# AteGates.net
KiCad netlist of a schematic drawn in EAGLE
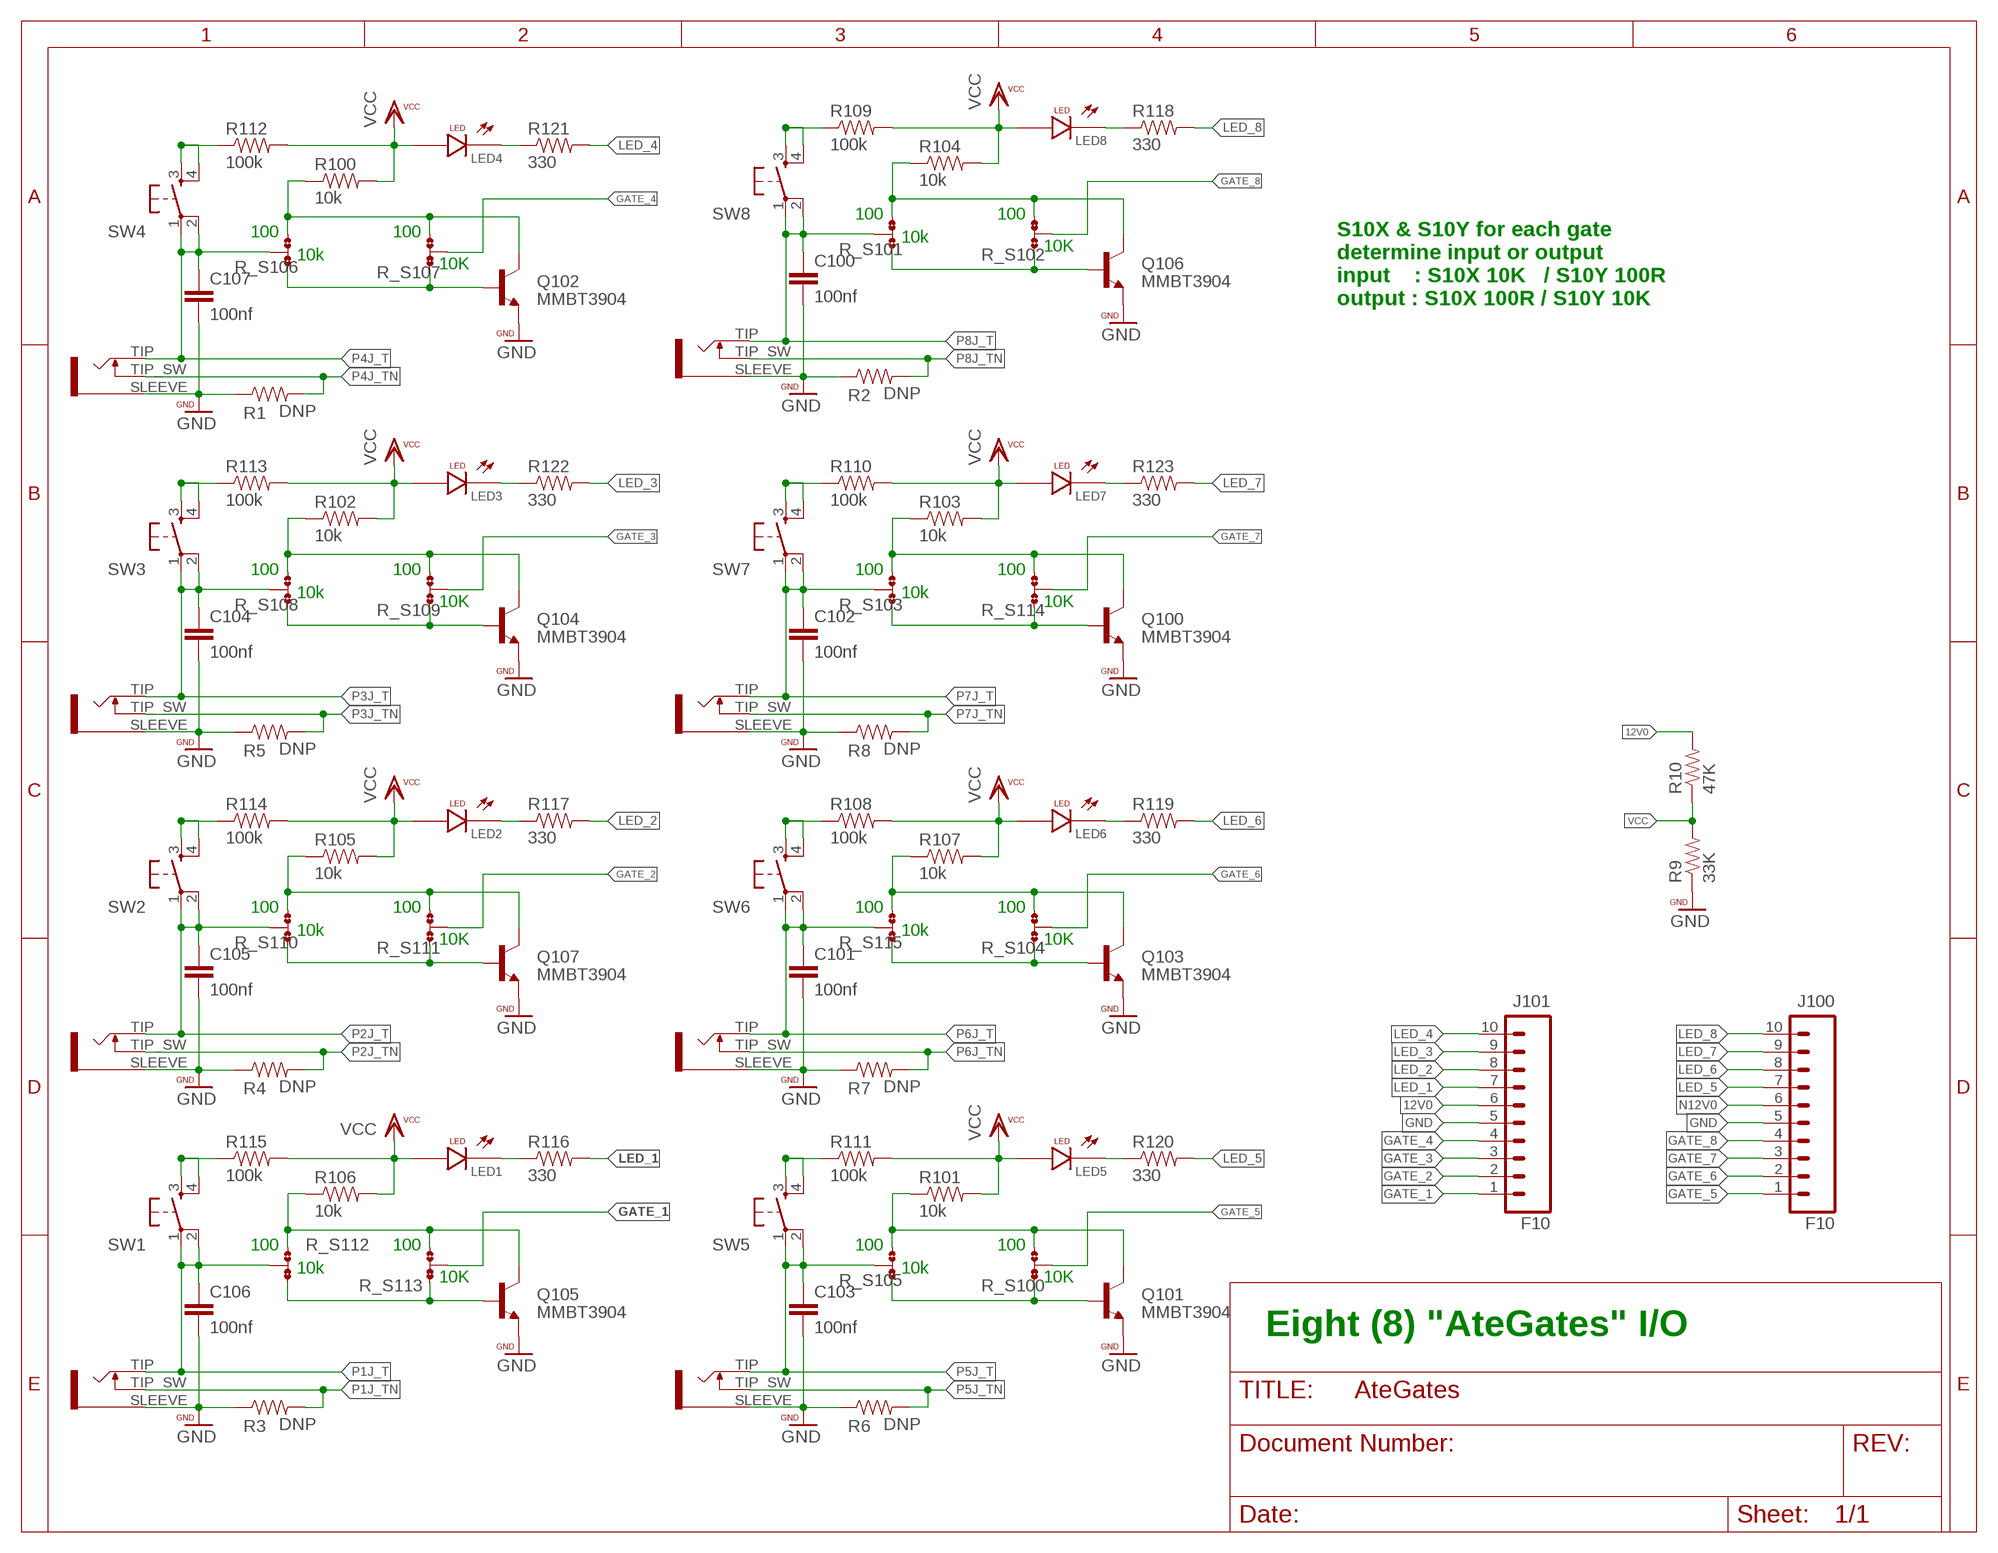
[diagram p0: schematic, sheet 1]

(export (version "E")
  (design (tool "Eeschema 10.0.6"))
  (components
    (comp (ref "C100")
      (value "100nf")
      (footprint "eagle-import:0603-CAP")
      (libsource (lib "eagle-import") (part "CAP0603-CAP"))
    )
    (comp (ref "C101")
      (value "100nf")
      (footprint "eagle-import:0603-CAP")
      (libsource (lib "eagle-import") (part "CAP0603-CAP"))
    )
    (comp (ref "C102")
      (value "100nf")
      (footprint "eagle-import:0603-CAP")
      (libsource (lib "eagle-import") (part "CAP0603-CAP"))
    )
    (comp (ref "C103")
      (value "100nf")
      (footprint "eagle-import:0603-CAP")
      (libsource (lib "eagle-import") (part "CAP0603-CAP"))
    )
    (comp (ref "C104")
      (value "100nf")
      (footprint "eagle-import:0603-CAP")
      (libsource (lib "eagle-import") (part "CAP0603-CAP"))
    )
    (comp (ref "C105")
      (value "100nf")
      (footprint "eagle-import:0603-CAP")
      (libsource (lib "eagle-import") (part "CAP0603-CAP"))
    )
    (comp (ref "C106")
      (value "100nf")
      (footprint "eagle-import:0603-CAP")
      (libsource (lib "eagle-import") (part "CAP0603-CAP"))
    )
    (comp (ref "C107")
      (value "100nf")
      (footprint "eagle-import:0603-CAP")
      (libsource (lib "eagle-import") (part "CAP0603-CAP"))
    )
    (comp (ref "J100")
      (value "F10")
      (footprint "eagle-import:1X10_OCTO")
      (libsource (lib "eagle-import") (part "M10SILK_FEMALE_PTH"))
    )
    (comp (ref "J101")
      (value "F10")
      (footprint "eagle-import:1X10_OCTO")
      (libsource (lib "eagle-import") (part "M10SILK_FEMALE_PTH"))
    )
    (comp (ref "LED1")
      (value "LED")
      (footprint "eagle-import:LED3MM")
      (libsource (lib "eagle-import") (part "LED"))
    )
    (comp (ref "LED2")
      (value "LED")
      (footprint "eagle-import:LED3MM")
      (libsource (lib "eagle-import") (part "LED"))
    )
    (comp (ref "LED3")
      (value "LED")
      (footprint "eagle-import:LED3MM")
      (libsource (lib "eagle-import") (part "LED"))
    )
    (comp (ref "LED4")
      (value "LED")
      (footprint "eagle-import:LED3MM")
      (libsource (lib "eagle-import") (part "LED"))
    )
    (comp (ref "LED5")
      (value "LED")
      (footprint "eagle-import:LED3MM")
      (libsource (lib "eagle-import") (part "LED"))
    )
    (comp (ref "LED6")
      (value "LED")
      (footprint "eagle-import:LED3MM")
      (libsource (lib "eagle-import") (part "LED"))
    )
    (comp (ref "LED7")
      (value "LED")
      (footprint "eagle-import:LED3MM")
      (libsource (lib "eagle-import") (part "LED"))
    )
    (comp (ref "LED8")
      (value "LED")
      (footprint "eagle-import:LED3MM")
      (libsource (lib "eagle-import") (part "LED"))
    )
    (comp (ref "P1J")
      (value "JACK-3_5MM-MONO-SW-WQP_PJ302-12")
      (footprint "eagle-import:WQP_PJ301M-12")
      (libsource (lib "eagle-import") (part "JACK-3_5MM-MONO-SW-WQP_PJ302-12"))
    )
    (comp (ref "P2J")
      (value "JACK-3_5MM-MONO-SW-WQP_PJ302-12")
      (footprint "eagle-import:WQP_PJ301M-12")
      (libsource (lib "eagle-import") (part "JACK-3_5MM-MONO-SW-WQP_PJ302-12"))
    )
    (comp (ref "P3J")
      (value "JACK-3_5MM-MONO-SW-WQP_PJ302-12")
      (footprint "eagle-import:WQP_PJ301M-12")
      (libsource (lib "eagle-import") (part "JACK-3_5MM-MONO-SW-WQP_PJ302-12"))
    )
    (comp (ref "P4J")
      (value "JACK-3_5MM-MONO-SW-WQP_PJ302-12")
      (footprint "eagle-import:WQP_PJ301M-12")
      (libsource (lib "eagle-import") (part "JACK-3_5MM-MONO-SW-WQP_PJ302-12"))
    )
    (comp (ref "P5J")
      (value "JACK-3_5MM-MONO-SW-WQP_PJ302-12")
      (footprint "eagle-import:WQP_PJ301M-12")
      (libsource (lib "eagle-import") (part "JACK-3_5MM-MONO-SW-WQP_PJ302-12"))
    )
    (comp (ref "P6J")
      (value "JACK-3_5MM-MONO-SW-WQP_PJ302-12")
      (footprint "eagle-import:WQP_PJ301M-12")
      (libsource (lib "eagle-import") (part "JACK-3_5MM-MONO-SW-WQP_PJ302-12"))
    )
    (comp (ref "P7J")
      (value "JACK-3_5MM-MONO-SW-WQP_PJ302-12")
      (footprint "eagle-import:WQP_PJ301M-12")
      (libsource (lib "eagle-import") (part "JACK-3_5MM-MONO-SW-WQP_PJ302-12"))
    )
    (comp (ref "P8J")
      (value "JACK-3_5MM-MONO-SW-WQP_PJ302-12")
      (footprint "eagle-import:WQP_PJ301M-12")
      (libsource (lib "eagle-import") (part "JACK-3_5MM-MONO-SW-WQP_PJ302-12"))
    )
    (comp (ref "Q100")
      (value "MMBT3904")
      (footprint "eagle-import:SOT23-BEC")
      (libsource (lib "eagle-import") (part "-NPN-SOT23-BECMMBT3904LT1"))
    )
    (comp (ref "Q101")
      (value "MMBT3904")
      (footprint "eagle-import:SOT23-BEC")
      (libsource (lib "eagle-import") (part "-NPN-SOT23-BECMMBT3904LT1"))
    )
    (comp (ref "Q102")
      (value "MMBT3904")
      (footprint "eagle-import:SOT23-BEC")
      (libsource (lib "eagle-import") (part "-NPN-SOT23-BECMMBT3904LT1"))
    )
    (comp (ref "Q103")
      (value "MMBT3904")
      (footprint "eagle-import:SOT23-BEC")
      (libsource (lib "eagle-import") (part "-NPN-SOT23-BECMMBT3904LT1"))
    )
    (comp (ref "Q104")
      (value "MMBT3904")
      (footprint "eagle-import:SOT23-BEC")
      (libsource (lib "eagle-import") (part "-NPN-SOT23-BECMMBT3904LT1"))
    )
    (comp (ref "Q105")
      (value "MMBT3904")
      (footprint "eagle-import:SOT23-BEC")
      (libsource (lib "eagle-import") (part "-NPN-SOT23-BECMMBT3904LT1"))
    )
    (comp (ref "Q106")
      (value "MMBT3904")
      (footprint "eagle-import:SOT23-BEC")
      (libsource (lib "eagle-import") (part "-NPN-SOT23-BECMMBT3904LT1"))
    )
    (comp (ref "Q107")
      (value "MMBT3904")
      (footprint "eagle-import:SOT23-BEC")
      (libsource (lib "eagle-import") (part "-NPN-SOT23-BECMMBT3904LT1"))
    )
    (comp (ref "R1")
      (value "DNP")
      (footprint "eagle-import:0603-RES")
      (libsource (lib "eagle-import") (part "RESISTOR0603-RES"))
    )
    (comp (ref "R2")
      (value "DNP")
      (footprint "eagle-import:0603-RES")
      (libsource (lib "eagle-import") (part "RESISTOR0603-RES"))
    )
    (comp (ref "R3")
      (value "DNP")
      (footprint "eagle-import:0603-RES")
      (libsource (lib "eagle-import") (part "RESISTOR0603-RES"))
    )
    (comp (ref "R4")
      (value "DNP")
      (footprint "eagle-import:0603-RES")
      (libsource (lib "eagle-import") (part "RESISTOR0603-RES"))
    )
    (comp (ref "R5")
      (value "DNP")
      (footprint "eagle-import:0603-RES")
      (libsource (lib "eagle-import") (part "RESISTOR0603-RES"))
    )
    (comp (ref "R6")
      (value "DNP")
      (footprint "eagle-import:0603-RES")
      (libsource (lib "eagle-import") (part "RESISTOR0603-RES"))
    )
    (comp (ref "R7")
      (value "DNP")
      (footprint "eagle-import:0603-RES")
      (libsource (lib "eagle-import") (part "RESISTOR0603-RES"))
    )
    (comp (ref "R8")
      (value "DNP")
      (footprint "eagle-import:0603-RES")
      (libsource (lib "eagle-import") (part "RESISTOR0603-RES"))
    )
    (comp (ref "R9")
      (value "33K")
      (footprint "eagle-import:0603-RES")
      (libsource (lib "eagle-import") (part "RESISTOR0603-RES"))
    )
    (comp (ref "R10")
      (value "47K")
      (footprint "eagle-import:0603-RES")
      (libsource (lib "eagle-import") (part "RESISTOR0603-RES"))
    )
    (comp (ref "R100")
      (value "10k")
      (footprint "eagle-import:0603-RES")
      (libsource (lib "eagle-import") (part "RESISTOR0603-RES"))
    )
    (comp (ref "R101")
      (value "10k")
      (footprint "eagle-import:0603-RES")
      (libsource (lib "eagle-import") (part "RESISTOR0603-RES"))
    )
    (comp (ref "R102")
      (value "10k")
      (footprint "eagle-import:0603-RES")
      (libsource (lib "eagle-import") (part "RESISTOR0603-RES"))
    )
    (comp (ref "R103")
      (value "10k")
      (footprint "eagle-import:0603-RES")
      (libsource (lib "eagle-import") (part "RESISTOR0603-RES"))
    )
    (comp (ref "R104")
      (value "10k")
      (footprint "eagle-import:0603-RES")
      (libsource (lib "eagle-import") (part "RESISTOR0603-RES"))
    )
    (comp (ref "R105")
      (value "10k")
      (footprint "eagle-import:0603-RES")
      (libsource (lib "eagle-import") (part "RESISTOR0603-RES"))
    )
    (comp (ref "R106")
      (value "10k")
      (footprint "eagle-import:0603-RES")
      (libsource (lib "eagle-import") (part "RESISTOR0603-RES"))
    )
    (comp (ref "R107")
      (value "10k")
      (footprint "eagle-import:0603-RES")
      (libsource (lib "eagle-import") (part "RESISTOR0603-RES"))
    )
    (comp (ref "R108")
      (value "100k")
      (footprint "eagle-import:0603-RES")
      (libsource (lib "eagle-import") (part "RESISTOR0603-RES"))
    )
    (comp (ref "R109")
      (value "100k")
      (footprint "eagle-import:0603-RES")
      (libsource (lib "eagle-import") (part "RESISTOR0603-RES"))
    )
    (comp (ref "R110")
      (value "100k")
      (footprint "eagle-import:0603-RES")
      (libsource (lib "eagle-import") (part "RESISTOR0603-RES"))
    )
    (comp (ref "R111")
      (value "100k")
      (footprint "eagle-import:0603-RES")
      (libsource (lib "eagle-import") (part "RESISTOR0603-RES"))
    )
    (comp (ref "R112")
      (value "100k")
      (footprint "eagle-import:0603-RES")
      (libsource (lib "eagle-import") (part "RESISTOR0603-RES"))
    )
    (comp (ref "R113")
      (value "100k")
      (footprint "eagle-import:0603-RES")
      (libsource (lib "eagle-import") (part "RESISTOR0603-RES"))
    )
    (comp (ref "R114")
      (value "100k")
      (footprint "eagle-import:0603-RES")
      (libsource (lib "eagle-import") (part "RESISTOR0603-RES"))
    )
    (comp (ref "R115")
      (value "100k")
      (footprint "eagle-import:0603-RES")
      (libsource (lib "eagle-import") (part "RESISTOR0603-RES"))
    )
    (comp (ref "R116")
      (value "330")
      (footprint "eagle-import:0603-RES")
      (libsource (lib "eagle-import") (part "RESISTOR0603-RES"))
    )
    (comp (ref "R117")
      (value "330")
      (footprint "eagle-import:0603-RES")
      (libsource (lib "eagle-import") (part "RESISTOR0603-RES"))
    )
    (comp (ref "R118")
      (value "330")
      (footprint "eagle-import:0603-RES")
      (libsource (lib "eagle-import") (part "RESISTOR0603-RES"))
    )
    (comp (ref "R119")
      (value "330")
      (footprint "eagle-import:0603-RES")
      (libsource (lib "eagle-import") (part "RESISTOR0603-RES"))
    )
    (comp (ref "R120")
      (value "330")
      (footprint "eagle-import:0603-RES")
      (libsource (lib "eagle-import") (part "RESISTOR0603-RES"))
    )
    (comp (ref "R121")
      (value "330")
      (footprint "eagle-import:0603-RES")
      (libsource (lib "eagle-import") (part "RESISTOR0603-RES"))
    )
    (comp (ref "R122")
      (value "330")
      (footprint "eagle-import:0603-RES")
      (libsource (lib "eagle-import") (part "RESISTOR0603-RES"))
    )
    (comp (ref "R123")
      (value "330")
      (footprint "eagle-import:0603-RES")
      (libsource (lib "eagle-import") (part "RESISTOR0603-RES"))
    )
    (comp (ref "R_S100")
      (value "JMP-3-NO-0603")
      (footprint "eagle-import:JMP-3-NO-0603")
      (libsource (lib "eagle-import") (part "JMP-3-NO-0603"))
    )
    (comp (ref "R_S101")
      (value "100")
      (footprint "eagle-import:JMP-3-NO-0603")
      (libsource (lib "eagle-import") (part "JMP-3-NO-0603"))
    )
    (comp (ref "R_S102")
      (value "JMP-3-NO-0603")
      (footprint "eagle-import:JMP-3-NO-0603")
      (libsource (lib "eagle-import") (part "JMP-3-NO-0603"))
    )
    (comp (ref "R_S103")
      (value "100")
      (footprint "eagle-import:JMP-3-NO-0603")
      (libsource (lib "eagle-import") (part "JMP-3-NO-0603"))
    )
    (comp (ref "R_S104")
      (value "JMP-3-NO-0603")
      (footprint "eagle-import:JMP-3-NO-0603")
      (libsource (lib "eagle-import") (part "JMP-3-NO-0603"))
    )
    (comp (ref "R_S105")
      (value "100")
      (footprint "eagle-import:JMP-3-NO-0603")
      (libsource (lib "eagle-import") (part "JMP-3-NO-0603"))
    )
    (comp (ref "R_S106")
      (value "100")
      (footprint "eagle-import:JMP-3-NO-0603")
      (libsource (lib "eagle-import") (part "JMP-3-NO-0603"))
    )
    (comp (ref "R_S107")
      (value "JMP-3-NO-0603")
      (footprint "eagle-import:JMP-3-NO-0603")
      (libsource (lib "eagle-import") (part "JMP-3-NO-0603"))
    )
    (comp (ref "R_S108")
      (value "100")
      (footprint "eagle-import:JMP-3-NO-0603")
      (libsource (lib "eagle-import") (part "JMP-3-NO-0603"))
    )
    (comp (ref "R_S109")
      (value "JMP-3-NO-0603")
      (footprint "eagle-import:JMP-3-NO-0603")
      (libsource (lib "eagle-import") (part "JMP-3-NO-0603"))
    )
    (comp (ref "R_S110")
      (value "100")
      (footprint "eagle-import:JMP-3-NO-0603")
      (libsource (lib "eagle-import") (part "JMP-3-NO-0603"))
    )
    (comp (ref "R_S111")
      (value "JMP-3-NO-0603")
      (footprint "eagle-import:JMP-3-NO-0603")
      (libsource (lib "eagle-import") (part "JMP-3-NO-0603"))
    )
    (comp (ref "R_S112")
      (value "100")
      (footprint "eagle-import:JMP-3-NO-0603")
      (libsource (lib "eagle-import") (part "JMP-3-NO-0603"))
    )
    (comp (ref "R_S113")
      (value "JMP-3-NO-0603")
      (footprint "eagle-import:JMP-3-NO-0603")
      (libsource (lib "eagle-import") (part "JMP-3-NO-0603"))
    )
    (comp (ref "R_S114")
      (value "JMP-3-NO-0603")
      (footprint "eagle-import:JMP-3-NO-0603")
      (libsource (lib "eagle-import") (part "JMP-3-NO-0603"))
    )
    (comp (ref "R_S115")
      (value "100")
      (footprint "eagle-import:JMP-3-NO-0603")
      (libsource (lib "eagle-import") (part "JMP-3-NO-0603"))
    )
    (comp (ref "SW1")
      (value "TAC_SWITCHPTH")
      (footprint "eagle-import:TACTILE-PTH")
      (libsource (lib "eagle-import") (part "TAC_SWITCHPTH"))
    )
    (comp (ref "SW2")
      (value "TAC_SWITCHPTH")
      (footprint "eagle-import:TACTILE-PTH")
      (libsource (lib "eagle-import") (part "TAC_SWITCHPTH"))
    )
    (comp (ref "SW3")
      (value "TAC_SWITCHPTH")
      (footprint "eagle-import:TACTILE-PTH")
      (libsource (lib "eagle-import") (part "TAC_SWITCHPTH"))
    )
    (comp (ref "SW4")
      (value "TAC_SWITCHPTH")
      (footprint "eagle-import:TACTILE-PTH")
      (libsource (lib "eagle-import") (part "TAC_SWITCHPTH"))
    )
    (comp (ref "SW5")
      (value "TAC_SWITCHPTH")
      (footprint "eagle-import:TACTILE-PTH")
      (libsource (lib "eagle-import") (part "TAC_SWITCHPTH"))
    )
    (comp (ref "SW6")
      (value "TAC_SWITCHPTH")
      (footprint "eagle-import:TACTILE-PTH")
      (libsource (lib "eagle-import") (part "TAC_SWITCHPTH"))
    )
    (comp (ref "SW7")
      (value "TAC_SWITCHPTH")
      (footprint "eagle-import:TACTILE-PTH")
      (libsource (lib "eagle-import") (part "TAC_SWITCHPTH"))
    )
    (comp (ref "SW8")
      (value "TAC_SWITCHPTH")
      (footprint "eagle-import:TACTILE-PTH")
      (libsource (lib "eagle-import") (part "TAC_SWITCHPTH"))
    )
  )
  (nets
    (net (code "1") (name "12V0") (class "Default")
      (node (ref "J101") (pin "6") (pinfunction "6_6") (pintype "passive"))
      (node (ref "R10") (pin "2") (pinfunction "2_2") (pintype "passive"))
    )
    (net (code "2") (name "GATE_1") (class "Default")
      (node (ref "J101") (pin "1") (pinfunction "1_1") (pintype "passive"))
      (node (ref "R_S113") (pin "2") (pinfunction "2_2") (pintype "passive"))
    )
    (net (code "3") (name "GATE_2") (class "Default")
      (node (ref "J101") (pin "2") (pinfunction "2_2") (pintype "passive"))
      (node (ref "R_S111") (pin "2") (pinfunction "2_2") (pintype "passive"))
    )
    (net (code "4") (name "GATE_3") (class "Default")
      (node (ref "J101") (pin "3") (pinfunction "3_3") (pintype "passive"))
      (node (ref "R_S109") (pin "2") (pinfunction "2_2") (pintype "passive"))
    )
    (net (code "5") (name "GATE_4") (class "Default")
      (node (ref "J101") (pin "4") (pinfunction "4_4") (pintype "passive"))
      (node (ref "R_S107") (pin "2") (pinfunction "2_2") (pintype "passive"))
    )
    (net (code "6") (name "GATE_5") (class "Default")
      (node (ref "J100") (pin "1") (pinfunction "1_1") (pintype "passive"))
      (node (ref "R_S100") (pin "2") (pinfunction "2_2") (pintype "passive"))
    )
    (net (code "7") (name "GATE_6") (class "Default")
      (node (ref "J100") (pin "2") (pinfunction "2_2") (pintype "passive"))
      (node (ref "R_S104") (pin "2") (pinfunction "2_2") (pintype "passive"))
    )
    (net (code "8") (name "GATE_7") (class "Default")
      (node (ref "J100") (pin "3") (pinfunction "3_3") (pintype "passive"))
      (node (ref "R_S114") (pin "2") (pinfunction "2_2") (pintype "passive"))
    )
    (net (code "9") (name "GATE_8") (class "Default")
      (node (ref "J100") (pin "4") (pinfunction "4_4") (pintype "passive"))
      (node (ref "R_S102") (pin "2") (pinfunction "2_2") (pintype "passive"))
    )
    (net (code "10") (name "GND") (class "Default")
      (node (ref "C100") (pin "2") (pinfunction "2_2") (pintype "passive"))
      (node (ref "C101") (pin "2") (pinfunction "2_2") (pintype "passive"))
      (node (ref "C102") (pin "2") (pinfunction "2_2") (pintype "passive"))
      (node (ref "C103") (pin "2") (pinfunction "2_2") (pintype "passive"))
      (node (ref "C104") (pin "2") (pinfunction "2_2") (pintype "passive"))
      (node (ref "C105") (pin "2") (pinfunction "2_2") (pintype "passive"))
      (node (ref "C106") (pin "2") (pinfunction "2_2") (pintype "passive"))
      (node (ref "C107") (pin "2") (pinfunction "2_2") (pintype "passive"))
      (node (ref "J100") (pin "5") (pinfunction "5_5") (pintype "passive"))
      (node (ref "J101") (pin "5") (pinfunction "5_5") (pintype "passive"))
      (node (ref "P1J") (pin "SLEEVE") (pinfunction "SLEEVE_SLEEVE") (pintype "passive"))
      (node (ref "P2J") (pin "SLEEVE") (pinfunction "SLEEVE_SLEEVE") (pintype "passive"))
      (node (ref "P3J") (pin "SLEEVE") (pinfunction "SLEEVE_SLEEVE") (pintype "passive"))
      (node (ref "P4J") (pin "SLEEVE") (pinfunction "SLEEVE_SLEEVE") (pintype "passive"))
      (node (ref "P5J") (pin "SLEEVE") (pinfunction "SLEEVE_SLEEVE") (pintype "passive"))
      (node (ref "P6J") (pin "SLEEVE") (pinfunction "SLEEVE_SLEEVE") (pintype "passive"))
      (node (ref "P7J") (pin "SLEEVE") (pinfunction "SLEEVE_SLEEVE") (pintype "passive"))
      (node (ref "P8J") (pin "SLEEVE") (pinfunction "SLEEVE_SLEEVE") (pintype "passive"))
      (node (ref "Q100") (pin "E") (pinfunction "E_E") (pintype "passive"))
      (node (ref "Q101") (pin "E") (pinfunction "E_E") (pintype "passive"))
      (node (ref "Q102") (pin "E") (pinfunction "E_E") (pintype "passive"))
      (node (ref "Q103") (pin "E") (pinfunction "E_E") (pintype "passive"))
      (node (ref "Q104") (pin "E") (pinfunction "E_E") (pintype "passive"))
      (node (ref "Q105") (pin "E") (pinfunction "E_E") (pintype "passive"))
      (node (ref "Q106") (pin "E") (pinfunction "E_E") (pintype "passive"))
      (node (ref "Q107") (pin "E") (pinfunction "E_E") (pintype "passive"))
      (node (ref "R1") (pin "1") (pinfunction "1_1") (pintype "passive"))
      (node (ref "R2") (pin "1") (pinfunction "1_1") (pintype "passive"))
      (node (ref "R3") (pin "1") (pinfunction "1_1") (pintype "passive"))
      (node (ref "R4") (pin "1") (pinfunction "1_1") (pintype "passive"))
      (node (ref "R5") (pin "1") (pinfunction "1_1") (pintype "passive"))
      (node (ref "R6") (pin "1") (pinfunction "1_1") (pintype "passive"))
      (node (ref "R7") (pin "1") (pinfunction "1_1") (pintype "passive"))
      (node (ref "R8") (pin "1") (pinfunction "1_1") (pintype "passive"))
      (node (ref "R9") (pin "1") (pinfunction "1_1") (pintype "passive"))
    )
    (net (code "11") (name "LED_1") (class "Default")
      (node (ref "J101") (pin "7") (pinfunction "7_7") (pintype "passive"))
      (node (ref "R116") (pin "2") (pinfunction "2_2") (pintype "passive"))
    )
    (net (code "12") (name "LED_2") (class "Default")
      (node (ref "J101") (pin "8") (pinfunction "8_8") (pintype "passive"))
      (node (ref "R117") (pin "2") (pinfunction "2_2") (pintype "passive"))
    )
    (net (code "13") (name "LED_3") (class "Default")
      (node (ref "J101") (pin "9") (pinfunction "9_9") (pintype "passive"))
      (node (ref "R122") (pin "2") (pinfunction "2_2") (pintype "passive"))
    )
    (net (code "14") (name "LED_4") (class "Default")
      (node (ref "J101") (pin "10") (pinfunction "10_10") (pintype "passive"))
      (node (ref "R121") (pin "2") (pinfunction "2_2") (pintype "passive"))
    )
    (net (code "15") (name "LED_5") (class "Default")
      (node (ref "J100") (pin "7") (pinfunction "7_7") (pintype "passive"))
      (node (ref "R120") (pin "2") (pinfunction "2_2") (pintype "passive"))
    )
    (net (code "16") (name "LED_6") (class "Default")
      (node (ref "J100") (pin "8") (pinfunction "8_8") (pintype "passive"))
      (node (ref "R119") (pin "2") (pinfunction "2_2") (pintype "passive"))
    )
    (net (code "17") (name "LED_7") (class "Default")
      (node (ref "J100") (pin "9") (pinfunction "9_9") (pintype "passive"))
      (node (ref "R123") (pin "2") (pinfunction "2_2") (pintype "passive"))
    )
    (net (code "18") (name "LED_8") (class "Default")
      (node (ref "J100") (pin "10") (pinfunction "10_10") (pintype "passive"))
      (node (ref "R118") (pin "2") (pinfunction "2_2") (pintype "passive"))
    )
    (net (code "19") (name "N12V0") (class "Default")
      (node (ref "J100") (pin "6") (pinfunction "6_6") (pintype "passive"))
    )
    (net (code "20") (name "Net-(LED1-CATHODE)") (class "Default")
      (node (ref "LED1") (pin "K") (pinfunction "CATHODE_K") (pintype "bidirectional"))
      (node (ref "R116") (pin "1") (pinfunction "1_1") (pintype "passive"))
    )
    (net (code "21") (name "Net-(LED2-CATHODE)") (class "Default")
      (node (ref "LED2") (pin "K") (pinfunction "CATHODE_K") (pintype "bidirectional"))
      (node (ref "R117") (pin "1") (pinfunction "1_1") (pintype "passive"))
    )
    (net (code "22") (name "Net-(LED3-CATHODE)") (class "Default")
      (node (ref "LED3") (pin "K") (pinfunction "CATHODE_K") (pintype "bidirectional"))
      (node (ref "R122") (pin "1") (pinfunction "1_1") (pintype "passive"))
    )
    (net (code "23") (name "Net-(LED4-CATHODE)") (class "Default")
      (node (ref "LED4") (pin "K") (pinfunction "CATHODE_K") (pintype "bidirectional"))
      (node (ref "R121") (pin "1") (pinfunction "1_1") (pintype "passive"))
    )
    (net (code "24") (name "Net-(LED5-CATHODE)") (class "Default")
      (node (ref "LED5") (pin "K") (pinfunction "CATHODE_K") (pintype "bidirectional"))
      (node (ref "R120") (pin "1") (pinfunction "1_1") (pintype "passive"))
    )
    (net (code "25") (name "Net-(LED6-CATHODE)") (class "Default")
      (node (ref "LED6") (pin "K") (pinfunction "CATHODE_K") (pintype "bidirectional"))
      (node (ref "R119") (pin "1") (pinfunction "1_1") (pintype "passive"))
    )
    (net (code "26") (name "Net-(LED7-CATHODE)") (class "Default")
      (node (ref "LED7") (pin "K") (pinfunction "CATHODE_K") (pintype "bidirectional"))
      (node (ref "R123") (pin "1") (pinfunction "1_1") (pintype "passive"))
    )
    (net (code "27") (name "Net-(LED8-CATHODE)") (class "Default")
      (node (ref "LED8") (pin "K") (pinfunction "CATHODE_K") (pintype "bidirectional"))
      (node (ref "R118") (pin "1") (pinfunction "1_1") (pintype "passive"))
    )
    (net (code "28") (name "Net-(Q100-PadB)") (class "Default")
      (node (ref "Q100") (pin "B") (pinfunction "B_B") (pintype "passive"))
      (node (ref "R_S103") (pin "3") (pinfunction "3_3") (pintype "passive"))
      (node (ref "R_S114") (pin "3") (pinfunction "3_3") (pintype "passive"))
    )
    (net (code "29") (name "Net-(Q100-PadC)") (class "Default")
      (node (ref "Q100") (pin "C") (pinfunction "C_C") (pintype "passive"))
      (node (ref "R103") (pin "1") (pinfunction "1_1") (pintype "passive"))
      (node (ref "R_S103") (pin "1") (pinfunction "1_1") (pintype "passive"))
      (node (ref "R_S114") (pin "1") (pinfunction "1_1") (pintype "passive"))
    )
    (net (code "30") (name "Net-(Q101-PadB)") (class "Default")
      (node (ref "Q101") (pin "B") (pinfunction "B_B") (pintype "passive"))
      (node (ref "R_S100") (pin "3") (pinfunction "3_3") (pintype "passive"))
      (node (ref "R_S105") (pin "3") (pinfunction "3_3") (pintype "passive"))
    )
    (net (code "31") (name "Net-(Q101-PadC)") (class "Default")
      (node (ref "Q101") (pin "C") (pinfunction "C_C") (pintype "passive"))
      (node (ref "R101") (pin "1") (pinfunction "1_1") (pintype "passive"))
      (node (ref "R_S100") (pin "1") (pinfunction "1_1") (pintype "passive"))
      (node (ref "R_S105") (pin "1") (pinfunction "1_1") (pintype "passive"))
    )
    (net (code "32") (name "Net-(Q102-PadB)") (class "Default")
      (node (ref "Q102") (pin "B") (pinfunction "B_B") (pintype "passive"))
      (node (ref "R_S106") (pin "3") (pinfunction "3_3") (pintype "passive"))
      (node (ref "R_S107") (pin "3") (pinfunction "3_3") (pintype "passive"))
    )
    (net (code "33") (name "Net-(Q102-PadC)") (class "Default")
      (node (ref "Q102") (pin "C") (pinfunction "C_C") (pintype "passive"))
      (node (ref "R100") (pin "1") (pinfunction "1_1") (pintype "passive"))
      (node (ref "R_S106") (pin "1") (pinfunction "1_1") (pintype "passive"))
      (node (ref "R_S107") (pin "1") (pinfunction "1_1") (pintype "passive"))
    )
    (net (code "34") (name "Net-(Q103-PadB)") (class "Default")
      (node (ref "Q103") (pin "B") (pinfunction "B_B") (pintype "passive"))
      (node (ref "R_S104") (pin "3") (pinfunction "3_3") (pintype "passive"))
      (node (ref "R_S115") (pin "3") (pinfunction "3_3") (pintype "passive"))
    )
    (net (code "35") (name "Net-(Q103-PadC)") (class "Default")
      (node (ref "Q103") (pin "C") (pinfunction "C_C") (pintype "passive"))
      (node (ref "R107") (pin "1") (pinfunction "1_1") (pintype "passive"))
      (node (ref "R_S104") (pin "1") (pinfunction "1_1") (pintype "passive"))
      (node (ref "R_S115") (pin "1") (pinfunction "1_1") (pintype "passive"))
    )
    (net (code "36") (name "Net-(Q104-PadB)") (class "Default")
      (node (ref "Q104") (pin "B") (pinfunction "B_B") (pintype "passive"))
      (node (ref "R_S108") (pin "3") (pinfunction "3_3") (pintype "passive"))
      (node (ref "R_S109") (pin "3") (pinfunction "3_3") (pintype "passive"))
    )
    (net (code "37") (name "Net-(Q104-PadC)") (class "Default")
      (node (ref "Q104") (pin "C") (pinfunction "C_C") (pintype "passive"))
      (node (ref "R102") (pin "1") (pinfunction "1_1") (pintype "passive"))
      (node (ref "R_S108") (pin "1") (pinfunction "1_1") (pintype "passive"))
      (node (ref "R_S109") (pin "1") (pinfunction "1_1") (pintype "passive"))
    )
    (net (code "38") (name "Net-(Q105-PadB)") (class "Default")
      (node (ref "Q105") (pin "B") (pinfunction "B_B") (pintype "passive"))
      (node (ref "R_S112") (pin "3") (pinfunction "3_3") (pintype "passive"))
      (node (ref "R_S113") (pin "3") (pinfunction "3_3") (pintype "passive"))
    )
    (net (code "39") (name "Net-(Q105-PadC)") (class "Default")
      (node (ref "Q105") (pin "C") (pinfunction "C_C") (pintype "passive"))
      (node (ref "R106") (pin "1") (pinfunction "1_1") (pintype "passive"))
      (node (ref "R_S112") (pin "1") (pinfunction "1_1") (pintype "passive"))
      (node (ref "R_S113") (pin "1") (pinfunction "1_1") (pintype "passive"))
    )
    (net (code "40") (name "Net-(Q106-PadB)") (class "Default")
      (node (ref "Q106") (pin "B") (pinfunction "B_B") (pintype "passive"))
      (node (ref "R_S101") (pin "3") (pinfunction "3_3") (pintype "passive"))
      (node (ref "R_S102") (pin "3") (pinfunction "3_3") (pintype "passive"))
    )
    (net (code "41") (name "Net-(Q106-PadC)") (class "Default")
      (node (ref "Q106") (pin "C") (pinfunction "C_C") (pintype "passive"))
      (node (ref "R104") (pin "1") (pinfunction "1_1") (pintype "passive"))
      (node (ref "R_S101") (pin "1") (pinfunction "1_1") (pintype "passive"))
      (node (ref "R_S102") (pin "1") (pinfunction "1_1") (pintype "passive"))
    )
    (net (code "42") (name "Net-(Q107-PadB)") (class "Default")
      (node (ref "Q107") (pin "B") (pinfunction "B_B") (pintype "passive"))
      (node (ref "R_S110") (pin "3") (pinfunction "3_3") (pintype "passive"))
      (node (ref "R_S111") (pin "3") (pinfunction "3_3") (pintype "passive"))
    )
    (net (code "43") (name "Net-(Q107-PadC)") (class "Default")
      (node (ref "Q107") (pin "C") (pinfunction "C_C") (pintype "passive"))
      (node (ref "R105") (pin "1") (pinfunction "1_1") (pintype "passive"))
      (node (ref "R_S110") (pin "1") (pinfunction "1_1") (pintype "passive"))
      (node (ref "R_S111") (pin "1") (pinfunction "1_1") (pintype "passive"))
    )
    (net (code "44") (name "Net-(R108-Pad1)") (class "Default")
      (node (ref "R108") (pin "1") (pinfunction "1_1") (pintype "passive"))
      (node (ref "SW6") (pin "3") (pinfunction "3_3") (pintype "passive"))
      (node (ref "SW6") (pin "4") (pinfunction "4_4") (pintype "passive"))
    )
    (net (code "45") (name "Net-(R109-Pad1)") (class "Default")
      (node (ref "R109") (pin "1") (pinfunction "1_1") (pintype "passive"))
      (node (ref "SW8") (pin "3") (pinfunction "3_3") (pintype "passive"))
      (node (ref "SW8") (pin "4") (pinfunction "4_4") (pintype "passive"))
    )
    (net (code "46") (name "Net-(R110-Pad1)") (class "Default")
      (node (ref "R110") (pin "1") (pinfunction "1_1") (pintype "passive"))
      (node (ref "SW7") (pin "3") (pinfunction "3_3") (pintype "passive"))
      (node (ref "SW7") (pin "4") (pinfunction "4_4") (pintype "passive"))
    )
    (net (code "47") (name "Net-(R111-Pad1)") (class "Default")
      (node (ref "R111") (pin "1") (pinfunction "1_1") (pintype "passive"))
      (node (ref "SW5") (pin "3") (pinfunction "3_3") (pintype "passive"))
      (node (ref "SW5") (pin "4") (pinfunction "4_4") (pintype "passive"))
    )
    (net (code "48") (name "Net-(R112-Pad1)") (class "Default")
      (node (ref "R112") (pin "1") (pinfunction "1_1") (pintype "passive"))
      (node (ref "SW4") (pin "3") (pinfunction "3_3") (pintype "passive"))
      (node (ref "SW4") (pin "4") (pinfunction "4_4") (pintype "passive"))
    )
    (net (code "49") (name "Net-(R113-Pad1)") (class "Default")
      (node (ref "R113") (pin "1") (pinfunction "1_1") (pintype "passive"))
      (node (ref "SW3") (pin "3") (pinfunction "3_3") (pintype "passive"))
      (node (ref "SW3") (pin "4") (pinfunction "4_4") (pintype "passive"))
    )
    (net (code "50") (name "Net-(R114-Pad1)") (class "Default")
      (node (ref "R114") (pin "1") (pinfunction "1_1") (pintype "passive"))
      (node (ref "SW2") (pin "3") (pinfunction "3_3") (pintype "passive"))
      (node (ref "SW2") (pin "4") (pinfunction "4_4") (pintype "passive"))
    )
    (net (code "51") (name "Net-(R115-Pad1)") (class "Default")
      (node (ref "R115") (pin "1") (pinfunction "1_1") (pintype "passive"))
      (node (ref "SW1") (pin "3") (pinfunction "3_3") (pintype "passive"))
      (node (ref "SW1") (pin "4") (pinfunction "4_4") (pintype "passive"))
    )
    (net (code "52") (name "P1J_T") (class "Default")
      (node (ref "C106") (pin "1") (pinfunction "1_1") (pintype "passive"))
      (node (ref "P1J") (pin "TIP") (pinfunction "TIP_TIP") (pintype "passive"))
      (node (ref "R_S112") (pin "2") (pinfunction "2_2") (pintype "passive"))
      (node (ref "SW1") (pin "1") (pinfunction "1_1") (pintype "passive"))
      (node (ref "SW1") (pin "2") (pinfunction "2_2") (pintype "passive"))
    )
    (net (code "53") (name "P1J_TN") (class "Default")
      (node (ref "P1J") (pin "TIP_SW") (pinfunction "TIP_SW_TIP_SW") (pintype "passive"))
      (node (ref "R3") (pin "2") (pinfunction "2_2") (pintype "passive"))
    )
    (net (code "54") (name "P2J_T") (class "Default")
      (node (ref "C105") (pin "1") (pinfunction "1_1") (pintype "passive"))
      (node (ref "P2J") (pin "TIP") (pinfunction "TIP_TIP") (pintype "passive"))
      (node (ref "R_S110") (pin "2") (pinfunction "2_2") (pintype "passive"))
      (node (ref "SW2") (pin "1") (pinfunction "1_1") (pintype "passive"))
      (node (ref "SW2") (pin "2") (pinfunction "2_2") (pintype "passive"))
    )
    (net (code "55") (name "P2J_TN") (class "Default")
      (node (ref "P2J") (pin "TIP_SW") (pinfunction "TIP_SW_TIP_SW") (pintype "passive"))
      (node (ref "R4") (pin "2") (pinfunction "2_2") (pintype "passive"))
    )
    (net (code "56") (name "P3J_T") (class "Default")
      (node (ref "C104") (pin "1") (pinfunction "1_1") (pintype "passive"))
      (node (ref "P3J") (pin "TIP") (pinfunction "TIP_TIP") (pintype "passive"))
      (node (ref "R_S108") (pin "2") (pinfunction "2_2") (pintype "passive"))
      (node (ref "SW3") (pin "1") (pinfunction "1_1") (pintype "passive"))
      (node (ref "SW3") (pin "2") (pinfunction "2_2") (pintype "passive"))
    )
    (net (code "57") (name "P3J_TN") (class "Default")
      (node (ref "P3J") (pin "TIP_SW") (pinfunction "TIP_SW_TIP_SW") (pintype "passive"))
      (node (ref "R5") (pin "2") (pinfunction "2_2") (pintype "passive"))
    )
    (net (code "58") (name "P4J_T") (class "Default")
      (node (ref "C107") (pin "1") (pinfunction "1_1") (pintype "passive"))
      (node (ref "P4J") (pin "TIP") (pinfunction "TIP_TIP") (pintype "passive"))
      (node (ref "R_S106") (pin "2") (pinfunction "2_2") (pintype "passive"))
      (node (ref "SW4") (pin "1") (pinfunction "1_1") (pintype "passive"))
      (node (ref "SW4") (pin "2") (pinfunction "2_2") (pintype "passive"))
    )
    (net (code "59") (name "P4J_TN") (class "Default")
      (node (ref "P4J") (pin "TIP_SW") (pinfunction "TIP_SW_TIP_SW") (pintype "passive"))
      (node (ref "R1") (pin "2") (pinfunction "2_2") (pintype "passive"))
    )
    (net (code "60") (name "P5J_T") (class "Default")
      (node (ref "C103") (pin "1") (pinfunction "1_1") (pintype "passive"))
      (node (ref "P5J") (pin "TIP") (pinfunction "TIP_TIP") (pintype "passive"))
      (node (ref "R_S105") (pin "2") (pinfunction "2_2") (pintype "passive"))
      (node (ref "SW5") (pin "1") (pinfunction "1_1") (pintype "passive"))
      (node (ref "SW5") (pin "2") (pinfunction "2_2") (pintype "passive"))
    )
    (net (code "61") (name "P5J_TN") (class "Default")
      (node (ref "P5J") (pin "TIP_SW") (pinfunction "TIP_SW_TIP_SW") (pintype "passive"))
      (node (ref "R6") (pin "2") (pinfunction "2_2") (pintype "passive"))
    )
    (net (code "62") (name "P6J_T") (class "Default")
      (node (ref "C101") (pin "1") (pinfunction "1_1") (pintype "passive"))
      (node (ref "P6J") (pin "TIP") (pinfunction "TIP_TIP") (pintype "passive"))
      (node (ref "R_S115") (pin "2") (pinfunction "2_2") (pintype "passive"))
      (node (ref "SW6") (pin "1") (pinfunction "1_1") (pintype "passive"))
      (node (ref "SW6") (pin "2") (pinfunction "2_2") (pintype "passive"))
    )
    (net (code "63") (name "P6J_TN") (class "Default")
      (node (ref "P6J") (pin "TIP_SW") (pinfunction "TIP_SW_TIP_SW") (pintype "passive"))
      (node (ref "R7") (pin "2") (pinfunction "2_2") (pintype "passive"))
    )
    (net (code "64") (name "P7J_T") (class "Default")
      (node (ref "C102") (pin "1") (pinfunction "1_1") (pintype "passive"))
      (node (ref "P7J") (pin "TIP") (pinfunction "TIP_TIP") (pintype "passive"))
      (node (ref "R_S103") (pin "2") (pinfunction "2_2") (pintype "passive"))
      (node (ref "SW7") (pin "1") (pinfunction "1_1") (pintype "passive"))
      (node (ref "SW7") (pin "2") (pinfunction "2_2") (pintype "passive"))
    )
    (net (code "65") (name "P7J_TN") (class "Default")
      (node (ref "P7J") (pin "TIP_SW") (pinfunction "TIP_SW_TIP_SW") (pintype "passive"))
      (node (ref "R8") (pin "2") (pinfunction "2_2") (pintype "passive"))
    )
    (net (code "66") (name "P8J_T") (class "Default")
      (node (ref "C100") (pin "1") (pinfunction "1_1") (pintype "passive"))
      (node (ref "P8J") (pin "TIP") (pinfunction "TIP_TIP") (pintype "passive"))
      (node (ref "R_S101") (pin "2") (pinfunction "2_2") (pintype "passive"))
      (node (ref "SW8") (pin "1") (pinfunction "1_1") (pintype "passive"))
      (node (ref "SW8") (pin "2") (pinfunction "2_2") (pintype "passive"))
    )
    (net (code "67") (name "P8J_TN") (class "Default")
      (node (ref "P8J") (pin "TIP_SW") (pinfunction "TIP_SW_TIP_SW") (pintype "passive"))
      (node (ref "R2") (pin "2") (pinfunction "2_2") (pintype "passive"))
    )
    (net (code "68") (name "VCC") (class "Default")
      (node (ref "LED1") (pin "A") (pinfunction "ANODE_A") (pintype "bidirectional"))
      (node (ref "LED2") (pin "A") (pinfunction "ANODE_A") (pintype "bidirectional"))
      (node (ref "LED3") (pin "A") (pinfunction "ANODE_A") (pintype "bidirectional"))
      (node (ref "LED4") (pin "A") (pinfunction "ANODE_A") (pintype "bidirectional"))
      (node (ref "LED5") (pin "A") (pinfunction "ANODE_A") (pintype "bidirectional"))
      (node (ref "LED6") (pin "A") (pinfunction "ANODE_A") (pintype "bidirectional"))
      (node (ref "LED7") (pin "A") (pinfunction "ANODE_A") (pintype "bidirectional"))
      (node (ref "LED8") (pin "A") (pinfunction "ANODE_A") (pintype "bidirectional"))
      (node (ref "R10") (pin "1") (pinfunction "1_1") (pintype "passive"))
      (node (ref "R100") (pin "2") (pinfunction "2_2") (pintype "passive"))
      (node (ref "R101") (pin "2") (pinfunction "2_2") (pintype "passive"))
      (node (ref "R102") (pin "2") (pinfunction "2_2") (pintype "passive"))
      (node (ref "R103") (pin "2") (pinfunction "2_2") (pintype "passive"))
      (node (ref "R104") (pin "2") (pinfunction "2_2") (pintype "passive"))
      (node (ref "R105") (pin "2") (pinfunction "2_2") (pintype "passive"))
      (node (ref "R106") (pin "2") (pinfunction "2_2") (pintype "passive"))
      (node (ref "R107") (pin "2") (pinfunction "2_2") (pintype "passive"))
      (node (ref "R108") (pin "2") (pinfunction "2_2") (pintype "passive"))
      (node (ref "R109") (pin "2") (pinfunction "2_2") (pintype "passive"))
      (node (ref "R110") (pin "2") (pinfunction "2_2") (pintype "passive"))
      (node (ref "R111") (pin "2") (pinfunction "2_2") (pintype "passive"))
      (node (ref "R112") (pin "2") (pinfunction "2_2") (pintype "passive"))
      (node (ref "R113") (pin "2") (pinfunction "2_2") (pintype "passive"))
      (node (ref "R114") (pin "2") (pinfunction "2_2") (pintype "passive"))
      (node (ref "R115") (pin "2") (pinfunction "2_2") (pintype "passive"))
      (node (ref "R9") (pin "2") (pinfunction "2_2") (pintype "passive"))
    )
  )
)
